# STN1170_RN-42_Toplevel_Rev2.net
KiCad netlist of a schematic drawn in Altium Designer
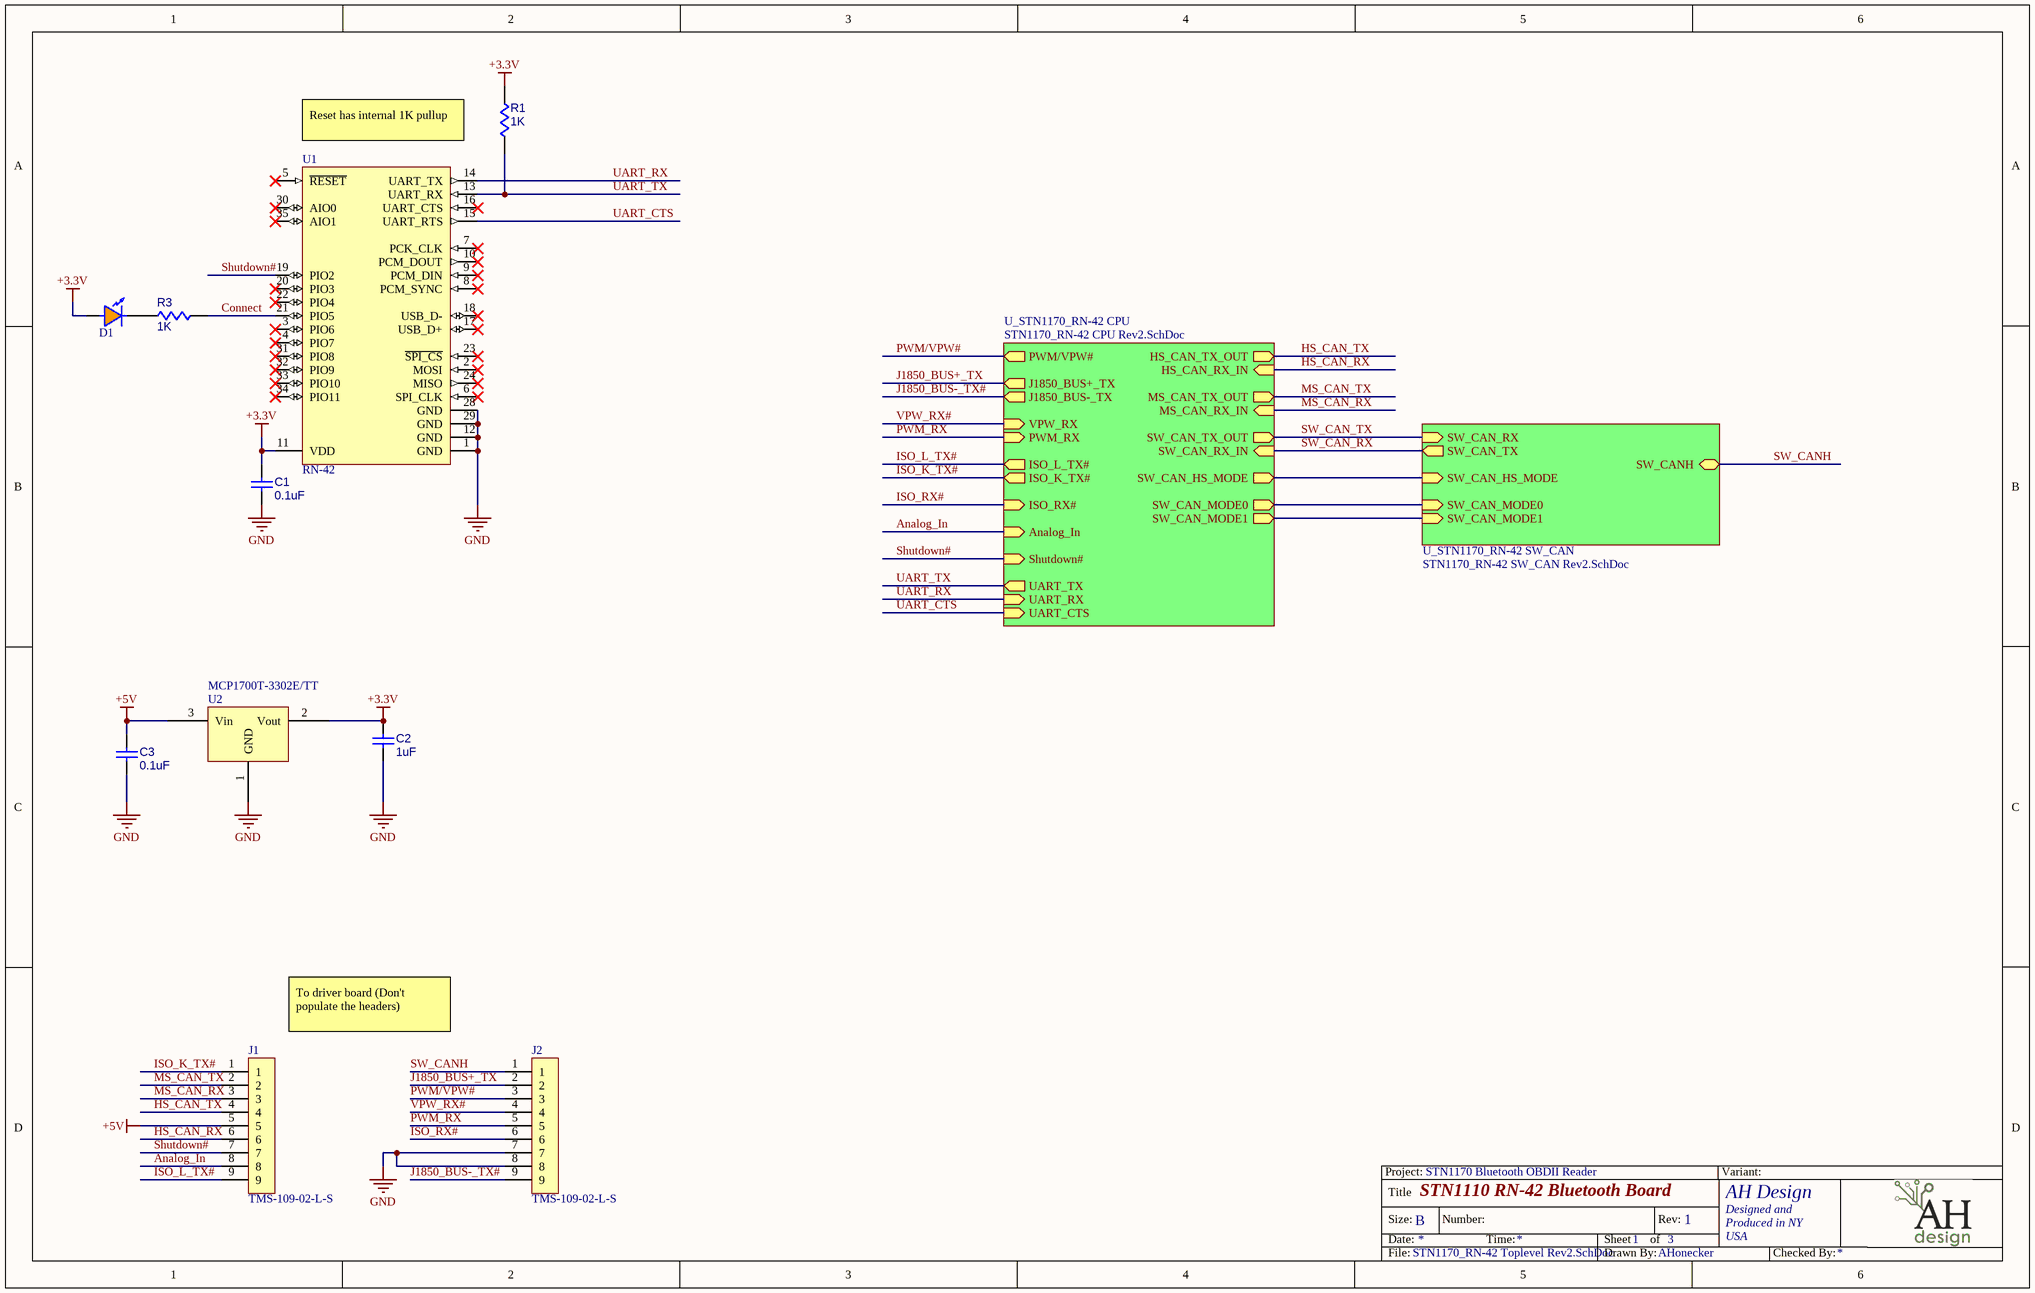
[diagram p0: STN1170_RN-42 Toplevel Rev2.SchDoc]

(export (version "E")
  (design (tool "Eeschema 10.0.6"))
  (components
    (comp (ref "C1")
      (value "0.1uF")
      (footprint "CC0603")
      (description "0.1uF 50V, in a CC0603, X7R ,+/-20%,LF")
      (fields
        (field (name "VOLTAGE") "50")
        (field (name "MANUFACTURER") "Kemet")
        (field (name "PUBLISHER") "AltiumdBManager")
        (field (name "APPROVED") "Pending")
      )
      (libsource (lib "VanteonStd") (part "CAP"))
    )
    (comp (ref "C2")
      (value "1uF")
      (footprint "CC0603")
      (description "1uF 6.3V, in a CC0603, X7R ,+/-20%,LF")
      (fields
        (field (name "VOLTAGE") "6.3")
        (field (name "MANUFACTURER") "Kemet Electronics Corp")
        (field (name "PUBLISHER") "AltiumDBManager1.4-MWyman")
        (field (name "APPROVED") "Yes")
        (field (name "APPROVER") "IHS")
      )
      (libsource (lib "VanteonStd") (part "CAP"))
    )
    (comp (ref "C3")
      (value "0.1uF")
      (footprint "CC0603")
      (description "0.1uF 50V, in a CC0603, X7R ,+/-20%,LF")
      (fields
        (field (name "VOLTAGE") "50")
        (field (name "MANUFACTURER") "Kemet")
        (field (name "PUBLISHER") "AltiumdBManager")
        (field (name "APPROVED") "Pending")
      )
      (libsource (lib "VanteonStd") (part "CAP"))
    )
    (comp (ref "D1")
      (value "APA1606SECK")
      (footprint "KINGBRIGHT_APA1606SECK")
      (description "LED 1.6X0.6MM 601NM Orange Right-Angle SMD")
      (fields
        (field (name "MANUFACTURER") "Kingbright Corp.")
        (field (name "APPROVED") "No")
        (field (name "PUBLISHER") "Vanteon - AHonecker")
      )
      (libsource (lib "AndyHoneckerNewComp") (part "KINGBRIGHT_APA1606SECK"))
    )
    (comp (ref "J1")
      (value "TMS-109-02-L-S")
      (footprint "Samtec_TMS-109-02-L-S")
      (description "9 pin through hole micro header, 50mil pitch")
      (fields (field (name "MANUFACTURER") "Samtec"))
      (libsource (lib "Andy_Parts") (part "Samtec_TMS-109-02-L-S"))
    )
    (comp (ref "J2")
      (value "TMS-109-02-L-S")
      (footprint "Samtec_TMS-109-02-L-S")
      (description "9 pin through hole micro header, 50mil pitch")
      (fields (field (name "MANUFACTURER") "Samtec"))
      (libsource (lib "Andy_Parts") (part "Samtec_TMS-109-02-L-S"))
    )
    (comp (ref "R1")
      (value "1K")
      (footprint "R0603")
      (description "1K, Gen Purp Chip, R0603 0.1W 5%")
      (fields
        (field (name "MANUFACTURER") "Panasonic")
        (field (name "PARTNUMBER") "ERJ3GEYJ102V")
        (field (name "PUBLISHER") "AltiumDBManager1.1")
      )
      (libsource (lib "VanteonStd") (part "RES"))
    )
    (comp (ref "R3")
      (value "1K")
      (footprint "R0603")
      (description "1K, Gen Purp Chip, R0603 0.1W 5%")
      (fields
        (field (name "MANUFACTURER") "Panasonic")
        (field (name "PARTNUMBER") "ERJ3GEYJ102V")
        (field (name "PUBLISHER") "AltiumDBManager1.1")
      )
      (libsource (lib "VanteonStd") (part "RES"))
    )
    (comp (ref "U1")
      (value "RN-42")
      (footprint "RN-42")
      (description "Roving Networks Bluetooth Serial Module")
      (fields (field (name "MANUFACTURER") "Roving Networks"))
      (libsource (lib "Andy_Parts") (part "RN-42"))
    )
    (comp (ref "U2")
      (value "MCP1700T-3302E/TT")
      (footprint "SOT23")
      (description "IC LDO REG 250MA 3.3V SOT-23-3")
      (fields (field (name "MANUFACTURER") "Microchip Technology"))
      (libsource (lib "Andy_Parts") (part "MCP1700T-3302E/TT"))
    )
  )
  (nets
    (net (code "1") (name "+3.3V") (class "Default")
      (node (ref "C1") (pin "1") (pinfunction "1_1") (pintype "passive"))
      (node (ref "C2") (pin "2") (pinfunction "2_2") (pintype "passive"))
      (node (ref "D1") (pin "A") (pinfunction "A_A") (pintype "passive"))
      (node (ref "R1") (pin "2") (pinfunction "2_2") (pintype "passive"))
      (node (ref "U1") (pin "11") (pinfunction "VDD_11") (pintype "power_in"))
      (node (ref "U2") (pin "2") (pinfunction "Vout_2") (pintype "power_in"))
    )
    (net (code "2") (name "+5V") (class "Default")
      (node (ref "C3") (pin "1") (pinfunction "1_1") (pintype "passive"))
      (node (ref "J1") (pin "5") (pinfunction "5_5") (pintype "passive"))
      (node (ref "U2") (pin "3") (pinfunction "Vin_3") (pintype "power_in"))
    )
    (net (code "3") (name "/Analog_In") (class "Default")
      (node (ref "J1") (pin "8") (pinfunction "8_8") (pintype "passive"))
    )
    (net (code "4") (name "/Connect") (class "Default")
      (node (ref "R3") (pin "2") (pinfunction "2_2") (pintype "passive"))
      (node (ref "U1") (pin "21") (pinfunction "PIO5_21") (pintype "bidirectional"))
    )
    (net (code "5") (name "/HS_CAN_RX") (class "Default")
      (node (ref "J1") (pin "6") (pinfunction "6_6") (pintype "passive"))
    )
    (net (code "6") (name "/HS_CAN_TX") (class "Default")
      (node (ref "J1") (pin "4") (pinfunction "4_4") (pintype "passive"))
    )
    (net (code "7") (name "/ISO_K_TX#") (class "Default")
      (node (ref "J1") (pin "1") (pinfunction "1_1") (pintype "passive"))
    )
    (net (code "8") (name "/ISO_L_TX#") (class "Default")
      (node (ref "J1") (pin "9") (pinfunction "9_9") (pintype "passive"))
    )
    (net (code "9") (name "/ISO_RX#") (class "Default")
      (node (ref "J2") (pin "6") (pinfunction "6_6") (pintype "passive"))
    )
    (net (code "10") (name "/J1850_BUS+_TX") (class "Default")
      (node (ref "J2") (pin "2") (pinfunction "2_2") (pintype "passive"))
    )
    (net (code "11") (name "/J1850_BUS-_TX#") (class "Default")
      (node (ref "J2") (pin "9") (pinfunction "9_9") (pintype "passive"))
    )
    (net (code "12") (name "/MS_CAN_RX") (class "Default")
      (node (ref "J1") (pin "3") (pinfunction "3_3") (pintype "passive"))
    )
    (net (code "13") (name "/MS_CAN_TX") (class "Default")
      (node (ref "J1") (pin "2") (pinfunction "2_2") (pintype "passive"))
    )
    (net (code "14") (name "/PWM_RX") (class "Default")
      (node (ref "J2") (pin "5") (pinfunction "5_5") (pintype "passive"))
    )
    (net (code "15") (name "/PWM{slash}VPW#") (class "Default")
      (node (ref "J2") (pin "3") (pinfunction "3_3") (pintype "passive"))
    )
    (net (code "16") (name "/SW_CANH") (class "Default")
      (node (ref "J2") (pin "1") (pinfunction "1_1") (pintype "passive"))
    )
    (net (code "22") (name "/Shutdown#") (class "Default")
      (node (ref "J1") (pin "7") (pinfunction "7_7") (pintype "passive"))
      (node (ref "U1") (pin "19") (pinfunction "PIO2_19") (pintype "bidirectional"))
    )
    (net (code "23") (name "/UART_CTS") (class "Default")
      (node (ref "U1") (pin "15") (pinfunction "UART_RTS_15") (pintype "output"))
    )
    (net (code "24") (name "/UART_RX") (class "Default")
      (node (ref "U1") (pin "14") (pinfunction "UART_TX_14") (pintype "output"))
    )
    (net (code "25") (name "/UART_TX") (class "Default")
      (node (ref "R1") (pin "1") (pinfunction "1_1") (pintype "passive"))
      (node (ref "U1") (pin "13") (pinfunction "UART_RX_13") (pintype "input"))
    )
    (net (code "26") (name "/VPW_RX#") (class "Default")
      (node (ref "J2") (pin "4") (pinfunction "4_4") (pintype "passive"))
    )
    (net (code "27") (name "GND") (class "Default")
      (node (ref "C1") (pin "2") (pinfunction "2_2") (pintype "passive"))
      (node (ref "C2") (pin "1") (pinfunction "1_1") (pintype "passive"))
      (node (ref "C3") (pin "2") (pinfunction "2_2") (pintype "passive"))
      (node (ref "J2") (pin "7") (pinfunction "7_7") (pintype "passive"))
      (node (ref "J2") (pin "8") (pinfunction "8_8") (pintype "passive"))
      (node (ref "U1") (pin "1") (pinfunction "GND_1") (pintype "power_in"))
      (node (ref "U1") (pin "12") (pinfunction "GND_12") (pintype "power_in"))
      (node (ref "U1") (pin "28") (pinfunction "GND_28") (pintype "power_in"))
      (node (ref "U1") (pin "29") (pinfunction "GND_29") (pintype "power_in"))
      (node (ref "U2") (pin "1") (pinfunction "GND_1") (pintype "power_in"))
    )
    (net (code "28") (name "Net-(D1-PadC)") (class "Default")
      (node (ref "D1") (pin "C") (pinfunction "C_C") (pintype "passive"))
      (node (ref "R3") (pin "1") (pinfunction "1_1") (pintype "passive"))
    )
    (net (code "29") (name "unconnected-(U1-AIO0-Pad30)") (class "Default")
      (node (ref "U1") (pin "30") (pinfunction "AIO0_30") (pintype "bidirectional+no_connect"))
    )
    (net (code "30") (name "unconnected-(U1-AIO1-Pad35)") (class "Default")
      (node (ref "U1") (pin "35") (pinfunction "AIO1_35") (pintype "bidirectional+no_connect"))
    )
    (net (code "31") (name "unconnected-(U1-MISO-Pad24)") (class "Default")
      (node (ref "U1") (pin "24") (pinfunction "MISO_24") (pintype "output+no_connect"))
    )
    (net (code "32") (name "unconnected-(U1-MOSI-Pad2)") (class "Default")
      (node (ref "U1") (pin "2") (pinfunction "MOSI_2") (pintype "input+no_connect"))
    )
    (net (code "33") (name "unconnected-(U1-PCK_CLK-Pad7)") (class "Default")
      (node (ref "U1") (pin "7") (pinfunction "PCK_CLK_7") (pintype "input+no_connect"))
    )
    (net (code "34") (name "unconnected-(U1-PCM_DIN-Pad9)") (class "Default")
      (node (ref "U1") (pin "9") (pinfunction "PCM_DIN_9") (pintype "input+no_connect"))
    )
    (net (code "35") (name "unconnected-(U1-PCM_DOUT-Pad10)") (class "Default")
      (node (ref "U1") (pin "10") (pinfunction "PCM_DOUT_10") (pintype "output+no_connect"))
    )
    (net (code "36") (name "unconnected-(U1-PCM_SYNC-Pad8)") (class "Default")
      (node (ref "U1") (pin "8") (pinfunction "PCM_SYNC_8") (pintype "input+no_connect"))
    )
    (net (code "37") (name "unconnected-(U1-PIO3-Pad20)") (class "Default")
      (node (ref "U1") (pin "20") (pinfunction "PIO3_20") (pintype "bidirectional+no_connect"))
    )
    (net (code "38") (name "unconnected-(U1-PIO4-Pad22)") (class "Default")
      (node (ref "U1") (pin "22") (pinfunction "PIO4_22") (pintype "bidirectional+no_connect"))
    )
    (net (code "39") (name "unconnected-(U1-PIO6-Pad3)") (class "Default")
      (node (ref "U1") (pin "3") (pinfunction "PIO6_3") (pintype "bidirectional+no_connect"))
    )
    (net (code "40") (name "unconnected-(U1-PIO7-Pad4)") (class "Default")
      (node (ref "U1") (pin "4") (pinfunction "PIO7_4") (pintype "bidirectional+no_connect"))
    )
    (net (code "41") (name "unconnected-(U1-PIO8-Pad31)") (class "Default")
      (node (ref "U1") (pin "31") (pinfunction "PIO8_31") (pintype "bidirectional+no_connect"))
    )
    (net (code "42") (name "unconnected-(U1-PIO9-Pad32)") (class "Default")
      (node (ref "U1") (pin "32") (pinfunction "PIO9_32") (pintype "bidirectional+no_connect"))
    )
    (net (code "43") (name "unconnected-(U1-PIO10-Pad33)") (class "Default")
      (node (ref "U1") (pin "33") (pinfunction "PIO10_33") (pintype "bidirectional+no_connect"))
    )
    (net (code "44") (name "unconnected-(U1-PIO11-Pad34)") (class "Default")
      (node (ref "U1") (pin "34") (pinfunction "PIO11_34") (pintype "bidirectional+no_connect"))
    )
    (net (code "45") (name "unconnected-(U1-SPI_CLK-Pad6)") (class "Default")
      (node (ref "U1") (pin "6") (pinfunction "SPI_CLK_6") (pintype "input+no_connect"))
    )
    (net (code "46") (name "unconnected-(U1-UART_CTS-Pad16)") (class "Default")
      (node (ref "U1") (pin "16") (pinfunction "UART_CTS_16") (pintype "input+no_connect"))
    )
    (net (code "47") (name "unconnected-(U1-USB_D+-Pad17)") (class "Default")
      (node (ref "U1") (pin "17") (pinfunction "USB_D+_17") (pintype "bidirectional+no_connect"))
    )
    (net (code "48") (name "unconnected-(U1-USB_D--Pad18)") (class "Default")
      (node (ref "U1") (pin "18") (pinfunction "USB_D-_18") (pintype "bidirectional+no_connect"))
    )
    (net (code "49") (name "unconnected-(U1-~{RESET}-Pad5)") (class "Default")
      (node (ref "U1") (pin "5") (pinfunction "~{RESET}_5") (pintype "input+no_connect"))
    )
    (net (code "50") (name "unconnected-(U1-~{SPI_CS}-Pad23)") (class "Default")
      (node (ref "U1") (pin "23") (pinfunction "~{SPI_CS}_23") (pintype "input+no_connect"))
    )
  )
)
